# radio.net
KiCad netlist of a schematic drawn in Altium Designer
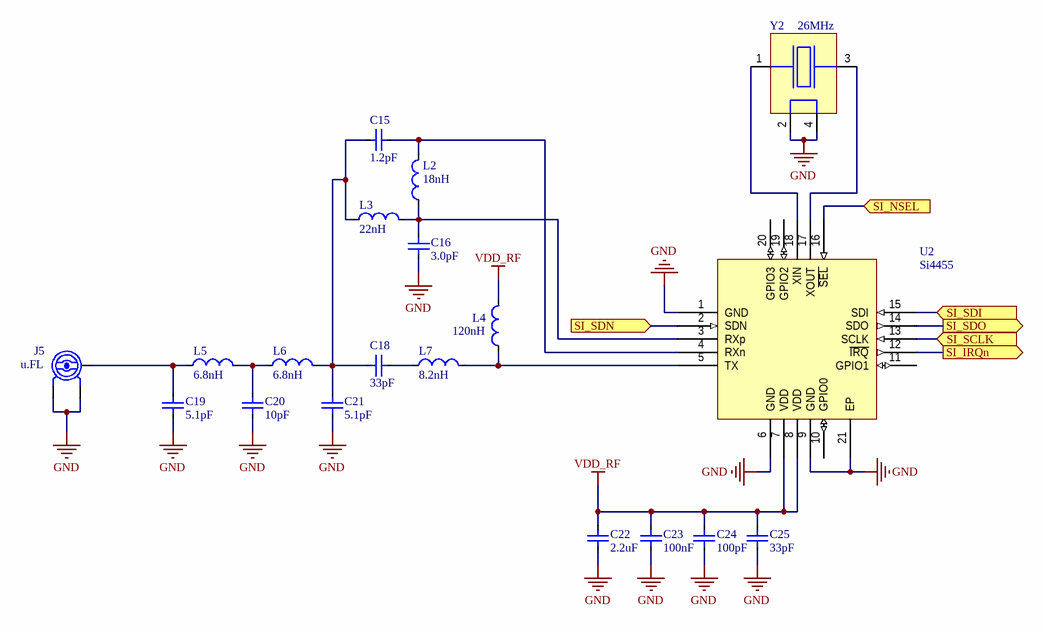
[diagram p0: radio.SchDoc]

(export (version "E")
  (design (tool "Eeschema 10.0.6"))
  (components
    (comp (ref "C15")
      (value "1.2pF")
      (footprint "0402_[1005]")
      (description "Capacitor")
      (libsource (lib "Discrete") (part "C"))
    )
    (comp (ref "C16")
      (value "3.0pF")
      (footprint "0402_[1005]")
      (description "Capacitor")
      (libsource (lib "Discrete") (part "C"))
    )
    (comp (ref "C18")
      (value "33pF")
      (footprint "0402_[1005]")
      (description "Capacitor")
      (libsource (lib "Discrete") (part "C"))
    )
    (comp (ref "C19")
      (value "5.1pF")
      (footprint "0402_[1005]")
      (description "Capacitor")
      (libsource (lib "Discrete") (part "C"))
    )
    (comp (ref "C20")
      (value "10pF")
      (footprint "0402_[1005]")
      (description "Capacitor")
      (libsource (lib "Discrete") (part "C"))
    )
    (comp (ref "C21")
      (value "5.1pF")
      (footprint "0402_[1005]")
      (description "Capacitor")
      (libsource (lib "Discrete") (part "C"))
    )
    (comp (ref "C22")
      (value "2.2uF")
      (footprint "0603_[1608]")
      (description "Capacitor")
      (libsource (lib "Discrete") (part "C"))
    )
    (comp (ref "C23")
      (value "100nF")
      (footprint "0402_[1005]")
      (description "Capacitor")
      (libsource (lib "Discrete") (part "C"))
    )
    (comp (ref "C24")
      (value "100pF")
      (footprint "0402_[1005]")
      (description "Capacitor")
      (libsource (lib "Discrete") (part "C"))
    )
    (comp (ref "C25")
      (value "33pF")
      (footprint "0402_[1005]")
      (description "Capacitor")
      (libsource (lib "Discrete") (part "C"))
    )
    (comp (ref "J5")
      (value "u.FL")
      (footprint "U.FL_COAXIAL_2.6x2.6MM_STRAIGHT_SMD")
      (description "u.FL antenna connector")
      (libsource (lib "Connectors") (part "u.FL"))
    )
    (comp (ref "L2")
      (value "18nH")
      (footprint "0402_[1005]")
      (description "Inductor")
      (libsource (lib "Discrete") (part "L"))
    )
    (comp (ref "L3")
      (value "22nH")
      (footprint "0402_[1005]")
      (description "Inductor")
      (libsource (lib "Discrete") (part "L"))
    )
    (comp (ref "L4")
      (value "120nH")
      (footprint "0402_[1005]")
      (description "Inductor")
      (libsource (lib "Discrete") (part "L"))
    )
    (comp (ref "L5")
      (value "6.8nH")
      (footprint "0402_[1005]")
      (description "Inductor")
      (libsource (lib "Discrete") (part "L"))
    )
    (comp (ref "L6")
      (value "6.8nH")
      (footprint "0402_[1005]")
      (description "Inductor")
      (libsource (lib "Discrete") (part "L"))
    )
    (comp (ref "L7")
      (value "8.2nH")
      (footprint "0402_[1005]")
      (description "Inductor")
      (libsource (lib "Discrete") (part "L"))
    )
    (comp (ref "U2")
      (value "Si4455")
      (footprint "QFN50P300X300X90_HS-21N")
      (description "Low-current OOK/(G)FSK sub-GHz transceiver")
      (libsource (lib "RF") (part "Si4455"))
    )
    (comp (ref "Y2")
      (value "26MHz")
      (footprint "CRYSTAL_2.5X2MM_4P_SMD")
      (description "Crystal oscillator, 4-pin")
      (libsource (lib "Discrete") (part "XTAL-4"))
    )
  )
  (nets
    (net (code "1") (name "/SI_IRQn") (class "Default")
      (node (ref "U2") (pin "12") (pinfunction "~{IRQ}_12") (pintype "output"))
    )
    (net (code "2") (name "/SI_NSEL") (class "Default")
      (node (ref "U2") (pin "16") (pinfunction "~{SEL}_16") (pintype "input"))
    )
    (net (code "3") (name "/SI_SCLK") (class "Default")
      (node (ref "U2") (pin "13") (pinfunction "SCLK_13") (pintype "input"))
    )
    (net (code "4") (name "/SI_SDI") (class "Default")
      (node (ref "U2") (pin "15") (pinfunction "SDI_15") (pintype "input"))
    )
    (net (code "5") (name "/SI_SDN") (class "Default")
      (node (ref "U2") (pin "2") (pinfunction "SDN_2") (pintype "input"))
    )
    (net (code "6") (name "/SI_SDO") (class "Default")
      (node (ref "U2") (pin "14") (pinfunction "SDO_14") (pintype "output"))
    )
    (net (code "7") (name "GND") (class "Default")
      (node (ref "C16") (pin "1") (pinfunction "1_1") (pintype "passive"))
      (node (ref "C19") (pin "1") (pinfunction "1_1") (pintype "passive"))
      (node (ref "C20") (pin "1") (pinfunction "1_1") (pintype "passive"))
      (node (ref "C21") (pin "1") (pinfunction "1_1") (pintype "passive"))
      (node (ref "C22") (pin "1") (pinfunction "1_1") (pintype "passive"))
      (node (ref "C23") (pin "1") (pinfunction "1_1") (pintype "passive"))
      (node (ref "C24") (pin "1") (pinfunction "1_1") (pintype "passive"))
      (node (ref "C25") (pin "1") (pinfunction "1_1") (pintype "passive"))
      (node (ref "J5") (pin "2") (pinfunction "GND_2") (pintype "power_in"))
      (node (ref "J5") (pin "3") (pinfunction "GND_3") (pintype "power_in"))
      (node (ref "U2") (pin "1") (pinfunction "GND_1") (pintype "power_in"))
      (node (ref "U2") (pin "21") (pinfunction "EP_21") (pintype "passive"))
      (node (ref "U2") (pin "6") (pinfunction "GND_6") (pintype "power_in"))
      (node (ref "U2") (pin "9") (pinfunction "GND_9") (pintype "power_in"))
      (node (ref "Y2") (pin "2") (pinfunction "2_2") (pintype "passive"))
      (node (ref "Y2") (pin "4") (pinfunction "4_4") (pintype "passive"))
    )
    (net (code "8") (name "Net-(C15-Pad1)") (class "Default")
      (node (ref "C15") (pin "1") (pinfunction "1_1") (pintype "passive"))
      (node (ref "C18") (pin "1") (pinfunction "1_1") (pintype "passive"))
      (node (ref "C21") (pin "2") (pinfunction "2_2") (pintype "passive"))
      (node (ref "L3") (pin "1") (pinfunction "1_1") (pintype "passive"))
      (node (ref "L6") (pin "2") (pinfunction "2_2") (pintype "passive"))
    )
    (net (code "9") (name "Net-(C18-Pad2)") (class "Default")
      (node (ref "C18") (pin "2") (pinfunction "2_2") (pintype "passive"))
      (node (ref "L7") (pin "1") (pinfunction "1_1") (pintype "passive"))
    )
    (net (code "10") (name "Net-(C20-Pad2)") (class "Default")
      (node (ref "C20") (pin "2") (pinfunction "2_2") (pintype "passive"))
      (node (ref "L5") (pin "2") (pinfunction "2_2") (pintype "passive"))
      (node (ref "L6") (pin "1") (pinfunction "1_1") (pintype "passive"))
    )
    (net (code "11") (name "Net-(J5-SIG)") (class "Default")
      (node (ref "C19") (pin "2") (pinfunction "2_2") (pintype "passive"))
      (node (ref "J5") (pin "1") (pinfunction "SIG_1") (pintype "passive"))
      (node (ref "L5") (pin "1") (pinfunction "1_1") (pintype "passive"))
    )
    (net (code "12") (name "Net-(U2-RXn)") (class "Default")
      (node (ref "C15") (pin "2") (pinfunction "2_2") (pintype "passive"))
      (node (ref "L2") (pin "2") (pinfunction "2_2") (pintype "passive"))
      (node (ref "U2") (pin "4") (pinfunction "RXn_4") (pintype "passive"))
    )
    (net (code "13") (name "Net-(U2-RXp)") (class "Default")
      (node (ref "C16") (pin "2") (pinfunction "2_2") (pintype "passive"))
      (node (ref "L2") (pin "1") (pinfunction "1_1") (pintype "passive"))
      (node (ref "L3") (pin "2") (pinfunction "2_2") (pintype "passive"))
      (node (ref "U2") (pin "3") (pinfunction "RXp_3") (pintype "passive"))
    )
    (net (code "14") (name "Net-(U2-TX)") (class "Default")
      (node (ref "L4") (pin "1") (pinfunction "1_1") (pintype "passive"))
      (node (ref "L7") (pin "2") (pinfunction "2_2") (pintype "passive"))
      (node (ref "U2") (pin "5") (pinfunction "TX_5") (pintype "passive"))
    )
    (net (code "15") (name "Net-(U2-XIN)") (class "Default")
      (node (ref "U2") (pin "18") (pinfunction "XIN_18") (pintype "passive"))
      (node (ref "Y2") (pin "1") (pinfunction "1_1") (pintype "passive"))
    )
    (net (code "16") (name "Net-(U2-XOUT)") (class "Default")
      (node (ref "U2") (pin "17") (pinfunction "XOUT_17") (pintype "passive"))
      (node (ref "Y2") (pin "3") (pinfunction "3_3") (pintype "passive"))
    )
    (net (code "17") (name "VDD_RF") (class "Default")
      (node (ref "C22") (pin "2") (pinfunction "2_2") (pintype "passive"))
      (node (ref "C23") (pin "2") (pinfunction "2_2") (pintype "passive"))
      (node (ref "C24") (pin "2") (pinfunction "2_2") (pintype "passive"))
      (node (ref "C25") (pin "2") (pinfunction "2_2") (pintype "passive"))
      (node (ref "L4") (pin "2") (pinfunction "2_2") (pintype "passive"))
      (node (ref "U2") (pin "7") (pinfunction "VDD_7") (pintype "power_in"))
      (node (ref "U2") (pin "8") (pinfunction "VDD_8") (pintype "power_in"))
    )
    (net (code "18") (name "unconnected-(U2-GPIO0-Pad10)") (class "Default")
      (node (ref "U2") (pin "10") (pinfunction "GPIO0_10") (pintype "bidirectional"))
    )
    (net (code "19") (name "unconnected-(U2-GPIO1-Pad11)") (class "Default")
      (node (ref "U2") (pin "11") (pinfunction "GPIO1_11") (pintype "bidirectional"))
    )
    (net (code "20") (name "unconnected-(U2-GPIO2-Pad19)") (class "Default")
      (node (ref "U2") (pin "19") (pinfunction "GPIO2_19") (pintype "bidirectional"))
    )
    (net (code "21") (name "unconnected-(U2-GPIO3-Pad20)") (class "Default")
      (node (ref "U2") (pin "20") (pinfunction "GPIO3_20") (pintype "bidirectional"))
    )
  )
)
